# HW15.net
KiCad netlist of a schematic drawn in Altium Designer
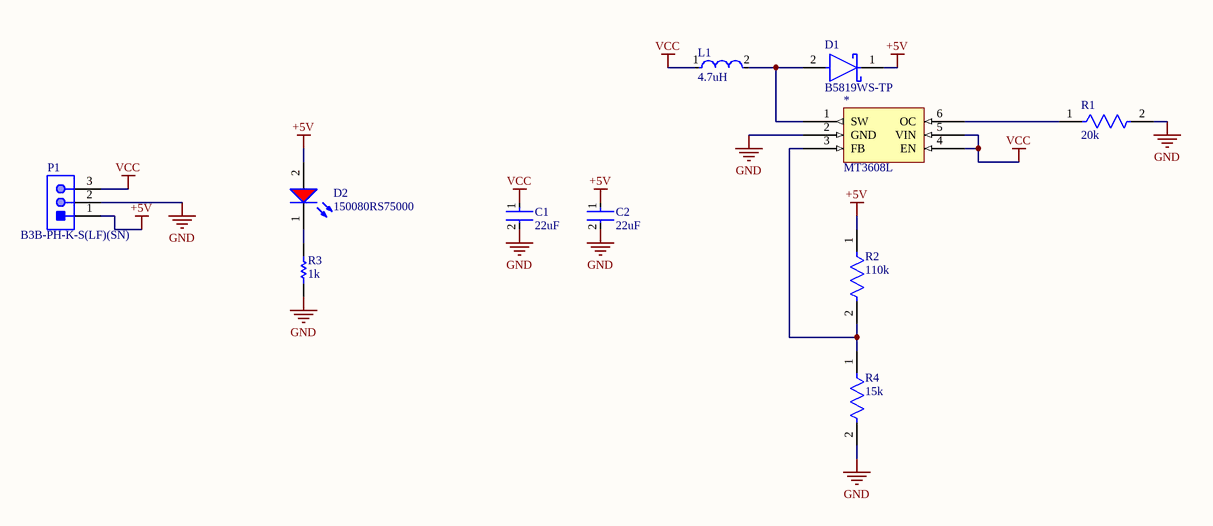
[diagram p0: HW15.SchDoc]

(export (version "E")
  (design (tool "Eeschema 10.0.6"))
  (components
    (comp (ref "*")
      (value "MT3608L")
      (footprint "SOT95P245X110-6N")
      (libsource (lib "Americas- Northwestern Formula Racing- Northwestern University") (part "MT3608L-Symbol-1"))
    )
    (comp (ref "C1")
      (value "22uF")
      (footprint "FP-GRM21B-0_15-MFG")
      (description "Chip Multilayer Ceramic Capacitors for General Purpose, 0805, 22uF, X5R, 15%, 20%, 6.3V")
      (fields (field (name "VOLTAGE") "6.3V") (field (name "TOLERANCE") "20%"))
      (libsource (lib "Altium Content Vault") (part "b4654b650e69147ec39a6b967a45e02"))
    )
    (comp (ref "C2")
      (value "22uF")
      (footprint "FP-GRM21B-0_15-MFG")
      (description "Chip Multilayer Ceramic Capacitors for General Purpose, 0805, 22uF, X5R, 15%, 20%, 6.3V")
      (fields (field (name "VOLTAGE") "6.3V") (field (name "TOLERANCE") "20%"))
      (libsource (lib "Altium Content Vault") (part "b4654b650e69147ec39a6b967a45e02"))
    )
    (comp (ref "D1")
      (value "B5819WS-TP")
      (footprint "FP-SOD-323-IPC_C")
      (description "DIODE SCHOTTKY 40V 1A SOD323")
      (libsource (lib "Altium Content Vault") (part "1d6ec82d83fb6aee721767c19dac4b9"))
    )
    (comp (ref "D2")
      (value "150080RS75000")
      (footprint "WL-SMCW_0805_150080xx75000")
      (description "LED Uni-Color Red 630nm 2-Pin Chip 0805(2012Metric) T/R")
      (libsource (lib "Altium Content Vault") (part "LED_Red_2A-1K"))
    )
    (comp (ref "L1")
      (value "4.7uH")
      (footprint "FP-IHLP-2525CZ-FP_2_413x3-MFG")
      (description "Commercial Inductors, High Saturation Series 4.7uH 5.5A 40mΩ 20%")
      (fields (field (name "TOLERANCE") "20%"))
      (libsource (lib "Altium Content Vault") (part "725321dda6339637d4d059423bc1c3c"))
    )
    (comp (ref "P1")
      (value "B3B-PH-K-S(LF)(SN)")
      (footprint "JST-B3B-PH-K-S-3_V")
      (fields (field (name "MANUFACTURER") "JST"))
      (libsource (lib "Altium Content Vault") (part "CN-1P-M-R3"))
    )
    (comp (ref "R1")
      (value "20k")
      (footprint "FP-ERA6A-MFG")
      (description "RES 20K OHM 0.1% 1/8W 0805")
      (fields (field (name "TOLERANCE") "0.1%"))
      (libsource (lib "Altium Content Vault") (part "1029c3af85768c4190bb7ad29bc67b5"))
    )
    (comp (ref "R2")
      (value "110k")
      (footprint "FP-CRCW0805-e3-MFG")
      (description "RES Thick Film, 110kΩ, 1%, 0.125W, 100ppm/°C, 0805")
      (fields (field (name "TOLERANCE") "1%"))
      (libsource (lib "Altium Content Vault") (part "1029c3af85768c4190bb7ad29bc67b5"))
    )
    (comp (ref "R3")
      (value "1k")
      (footprint "RESC2013X60X35ML10T20")
      (description "Chip Resistor, 1 KOhm, +/- 1%, 125 mW, -55 to 155 degC, 0805 (2012 Metric), RoHS, Tape and Reel")
      (fields (field (name "TOLERANCE") "1%") (field (name "MANUFACTURER") "Yageo"))
      (libsource (lib "Altium Content Vault") (part "RES-2"))
    )
    (comp (ref "R4")
      (value "15k")
      (footprint "FP-ERJ6EN-IPC_C")
      (description "RES SMD 15K OHM 1% 1/8W 0805")
      (fields (field (name "TOLERANCE") "1%"))
      (libsource (lib "Altium Content Vault") (part "8db39607336c341a927600551d01821"))
    )
  )
  (nets
    (net (code "1") (name "+5V") (class "Default")
      (node (ref "C2") (pin "1") (pinfunction "1_1") (pintype "passive"))
      (node (ref "D1") (pin "1") (pinfunction "C_1") (pintype "passive"))
      (node (ref "D2") (pin "2") (pinfunction "A_2") (pintype "passive"))
      (node (ref "P1") (pin "1") (pinfunction "1_1") (pintype "passive"))
      (node (ref "R2") (pin "1") (pinfunction "1_1") (pintype "passive"))
    )
    (net (code "2") (name "GND") (class "Default")
      (node (ref "*") (pin "2") (pinfunction "GND_2") (pintype "input"))
      (node (ref "C1") (pin "2") (pinfunction "2_2") (pintype "passive"))
      (node (ref "C2") (pin "2") (pinfunction "2_2") (pintype "passive"))
      (node (ref "P1") (pin "2") (pinfunction "2_2") (pintype "passive"))
      (node (ref "R1") (pin "2") (pinfunction "2_2") (pintype "passive"))
      (node (ref "R3") (pin "1") (pinfunction "1_1") (pintype "passive"))
      (node (ref "R4") (pin "2") (pinfunction "2_2") (pintype "passive"))
    )
    (net (code "3") (name "Net-(*-FB)") (class "Default")
      (node (ref "*") (pin "3") (pinfunction "FB_3") (pintype "input"))
      (node (ref "R2") (pin "2") (pinfunction "2_2") (pintype "passive"))
      (node (ref "R4") (pin "1") (pinfunction "1_1") (pintype "passive"))
    )
    (net (code "4") (name "Net-(*-OC)") (class "Default")
      (node (ref "*") (pin "6") (pinfunction "OC_6") (pintype "input"))
      (node (ref "R1") (pin "1") (pinfunction "1_1") (pintype "passive"))
    )
    (net (code "5") (name "Net-(*-SW)") (class "Default")
      (node (ref "*") (pin "1") (pinfunction "SW_1") (pintype "output"))
      (node (ref "D1") (pin "2") (pinfunction "A_2") (pintype "passive"))
      (node (ref "L1") (pin "2") (pinfunction "2_2") (pintype "passive"))
    )
    (net (code "6") (name "Net-(D2-K)") (class "Default")
      (node (ref "D2") (pin "1") (pinfunction "K_1") (pintype "passive"))
      (node (ref "R3") (pin "2") (pinfunction "2_2") (pintype "passive"))
    )
    (net (code "7") (name "VCC") (class "Default")
      (node (ref "*") (pin "4") (pinfunction "EN_4") (pintype "input"))
      (node (ref "*") (pin "5") (pinfunction "VIN_5") (pintype "input"))
      (node (ref "C1") (pin "1") (pinfunction "1_1") (pintype "passive"))
      (node (ref "L1") (pin "1") (pinfunction "1_1") (pintype "passive"))
      (node (ref "P1") (pin "3") (pinfunction "3_3") (pintype "passive"))
    )
  )
)
